# TSAL_Schematic.net
KiCad netlist of a schematic drawn in Altium Designer
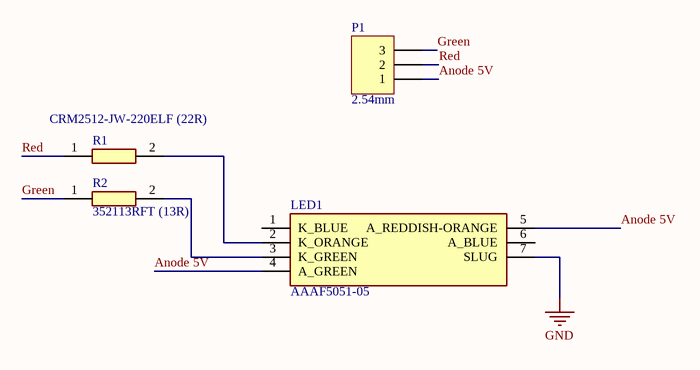
[diagram p0: TSAL_Schematic.SchDoc]

(export (version "E")
  (design (tool "Eeschema 10.0.6"))
  (components
    (comp (ref "LED1")
      (value "AAAF5051-05")
      (footprint "SamacSys:AAAF505105")
      (description "LED")
      (fields (field (name "MOUSER PART NUMBER") "604-AAAF5051-05"))
      (libsource (lib "*") (part "AAAF5051-05"))
    )
    (comp (ref "P1")
      (value "2.54mm")
      (footprint "TH 2.54mm Header 1x3")
      (fields (field (name "PART NUMBER") "TH 2.54mm Header 1x3") (field (name "CONTACT") "NA"))
      (libsource (lib "ts_20-standard-connectors") (part "Header 1x3"))
    )
    (comp (ref "R1")
      (value "CRM2512-JW-220ELF (22R)")
      (footprint "SamacSys:RESC6331X80N")
      (description "Resistor")
      (fields
        (field (name "MANUFACTURER_PART_NUMBER") "CRM2512-JW-220ELF")
        (field (name "MOUSER PART NUMBER") "652-CRM2512-JW220ELF")
      )
      (libsource (lib "*") (part "CRM2512-JW-220ELF"))
    )
    (comp (ref "R2")
      (value "352113RFT (13R)")
      (footprint "SamacSys:RESC6432X65N")
      (description "Resistor")
      (fields
        (field (name "MANUFACTURER_PART_NUMBER") "352113RFT")
        (field (name "MOUSER PART NUMBER") "279-352113RFT")
      )
      (libsource (lib "*") (part "352113RFT"))
    )
  )
  (nets
    (net (code "1") (name "/Anode 5V") (class "Default")
      (node (ref "LED1") (pin "4") (pinfunction "A_GREEN_4") (pintype "passive"))
      (node (ref "LED1") (pin "5") (pinfunction "A_REDDISH-ORANGE_5") (pintype "passive"))
      (node (ref "P1") (pin "1") (pinfunction "1_1") (pintype "passive"))
    )
    (net (code "2") (name "/Green") (class "Default")
      (node (ref "P1") (pin "3") (pinfunction "3_3") (pintype "passive"))
      (node (ref "R2") (pin "1") (pinfunction "1_1") (pintype "passive"))
    )
    (net (code "3") (name "/Red") (class "Default")
      (node (ref "P1") (pin "2") (pinfunction "2_2") (pintype "passive"))
      (node (ref "R1") (pin "1") (pinfunction "1_1") (pintype "passive"))
    )
    (net (code "4") (name "GND") (class "Default")
      (node (ref "LED1") (pin "7") (pinfunction "SLUG_7") (pintype "passive"))
    )
    (net (code "5") (name "Net-(LED1-K_GREEN)") (class "Default")
      (node (ref "LED1") (pin "3") (pinfunction "K_GREEN_3") (pintype "passive"))
      (node (ref "R2") (pin "2") (pinfunction "2_2") (pintype "passive"))
    )
    (net (code "6") (name "Net-(LED1-K_ORANGE)") (class "Default")
      (node (ref "LED1") (pin "2") (pinfunction "K_ORANGE_2") (pintype "passive"))
      (node (ref "R1") (pin "2") (pinfunction "2_2") (pintype "passive"))
    )
    (net (code "7") (name "unconnected-(LED1-A_BLUE-Pad6)") (class "Default")
      (node (ref "LED1") (pin "6") (pinfunction "A_BLUE_6") (pintype "passive"))
    )
    (net (code "8") (name "unconnected-(LED1-K_BLUE-Pad1)") (class "Default")
      (node (ref "LED1") (pin "1") (pinfunction "K_BLUE_1") (pintype "passive"))
    )
  )
)
